# IF_GAIN.net
KiCad netlist of a schematic drawn in Altium Designer
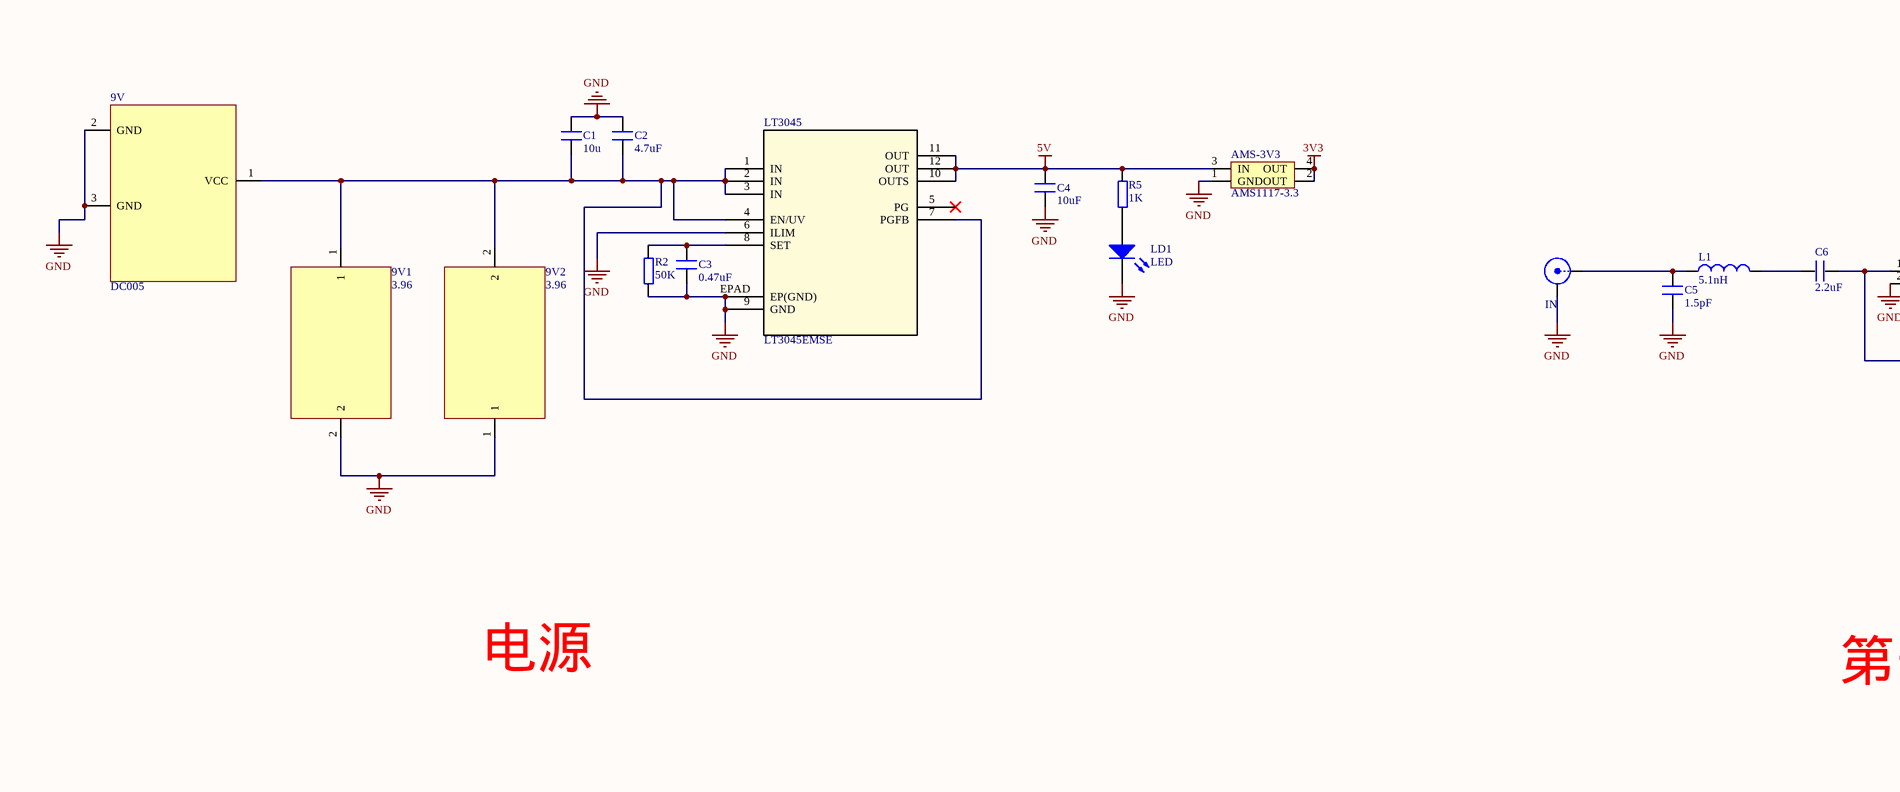
[diagram p0: IF GAIN].SchDoc, top left]
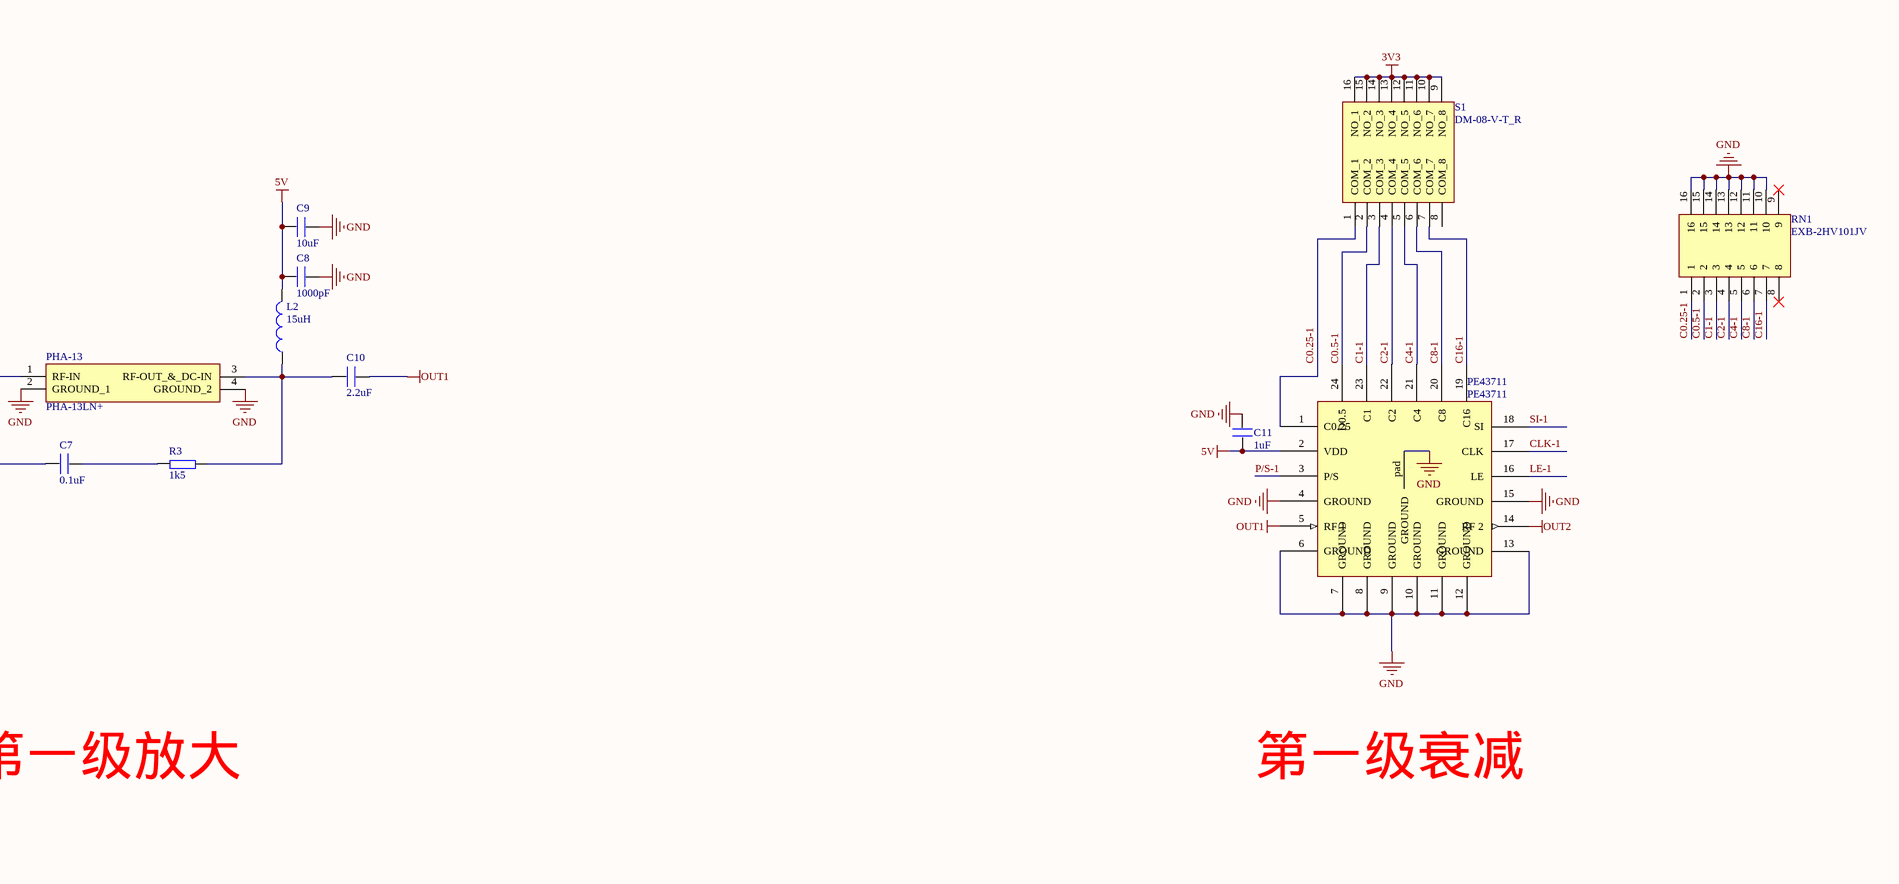
[diagram p1: IF GAIN].SchDoc, top right]
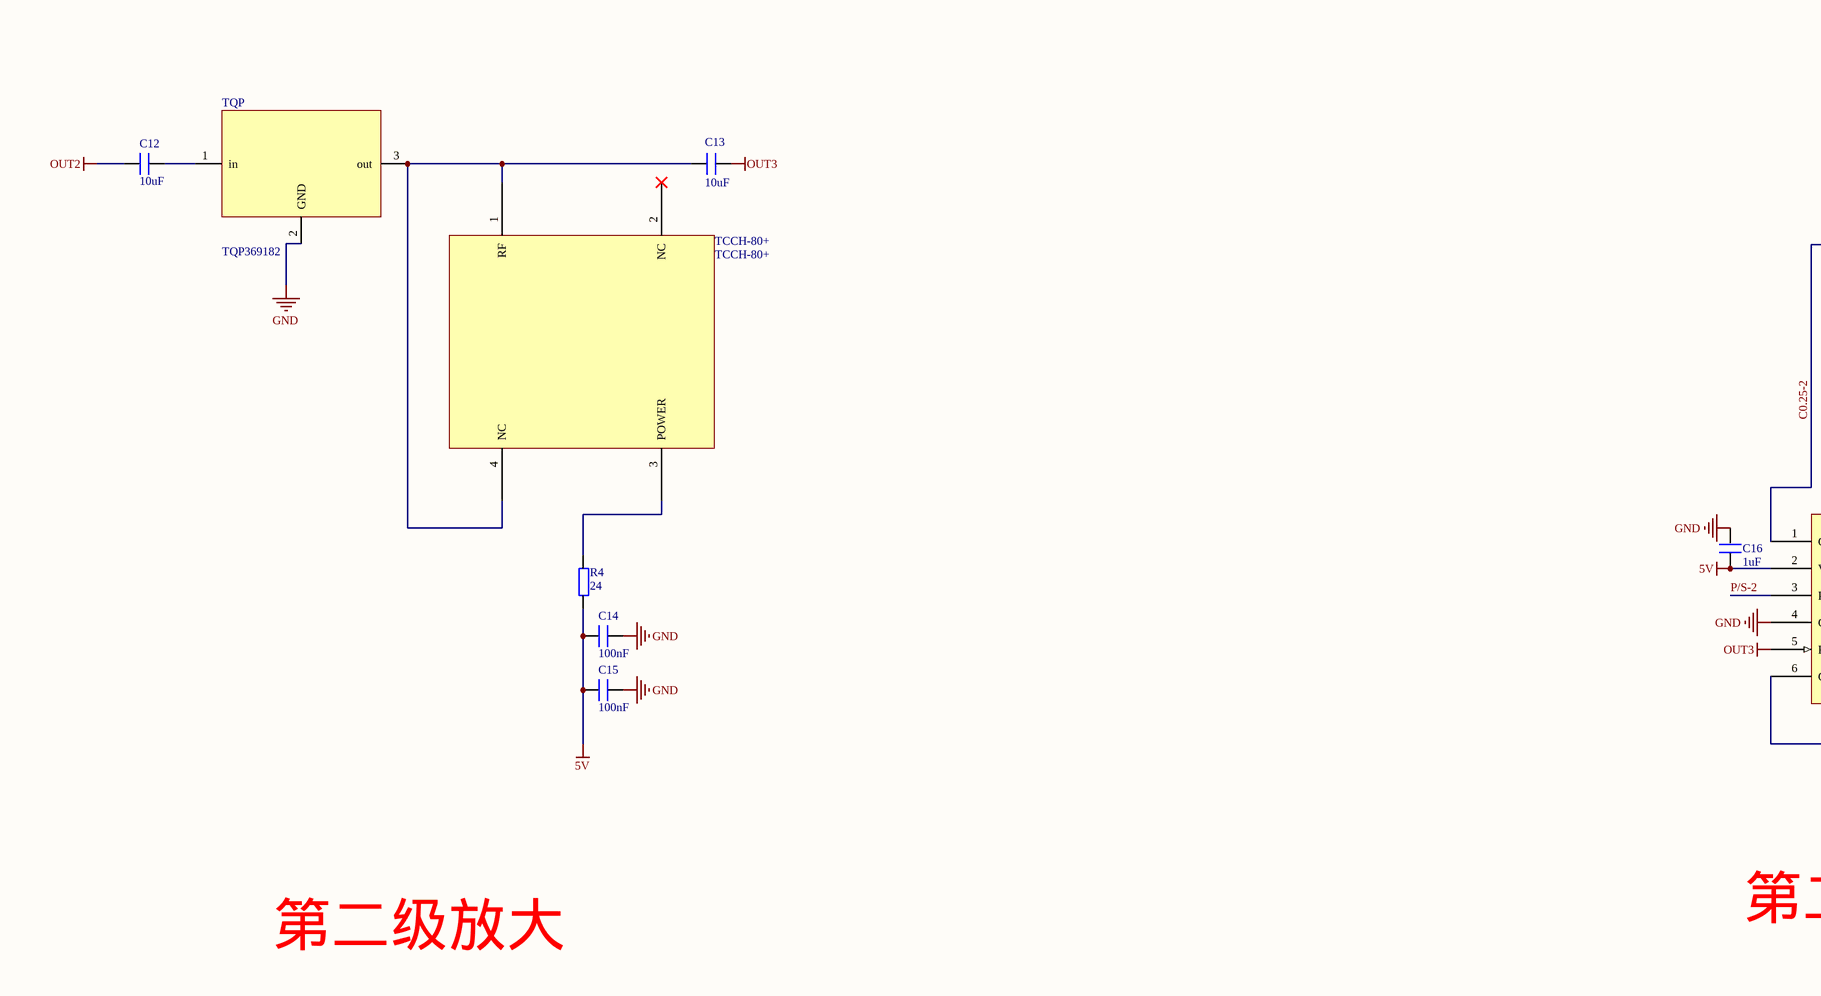
[diagram p2: IF GAIN].SchDoc, bottom left]
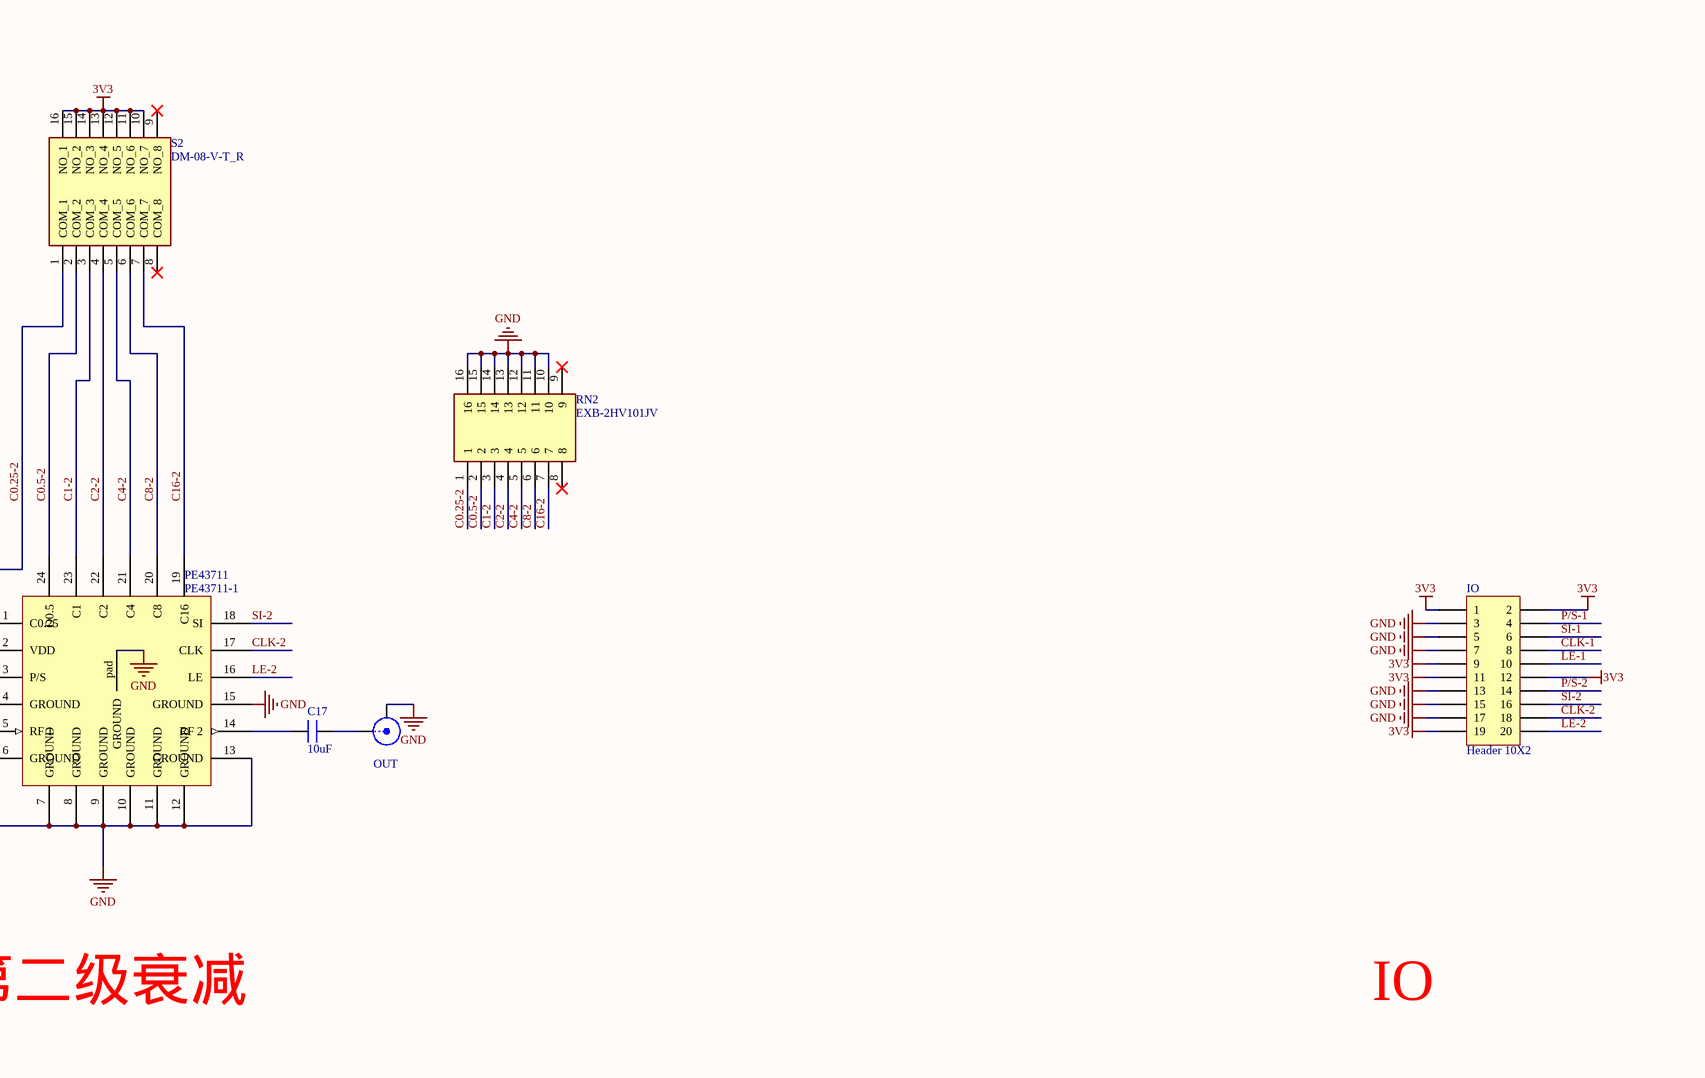
[diagram p3: IF GAIN].SchDoc, bottom right]

(export (version "E")
  (design (tool "Eeschema 10.0.6"))
  (components
    (comp (ref "9V") (value "DC005") (footprint "DC10B") (libsource (lib "MYLIB") (part "DC005")))
    (comp (ref "9V1") (value "3.96") (footprint "3.96") (libsource (lib "") (part "3.96_1")))
    (comp (ref "9V2") (value "3.96") (footprint "3.96") (libsource (lib "MYLIB") (part "3.96")))
    (comp (ref "AMS-3V3")
      (value "AMS1117-3.3")
      (footprint "AMS1117")
      (libsource (lib "MYLIB") (part "AMS1117"))
    )
    (comp (ref "C1")
      (value "10u")
      (footprint "0603C")
      (description "Capacitor")
      (libsource (lib "MYLIB") (part "C"))
    )
    (comp (ref "C2")
      (value "4.7uF")
      (footprint "0603C")
      (description "Capacitor")
      (libsource (lib "MYLIB") (part "C"))
    )
    (comp (ref "C3")
      (value "0.47uF")
      (footprint "0402")
      (description "Capacitor")
      (libsource (lib "MYLIB") (part "C"))
    )
    (comp (ref "C4")
      (value "10uF")
      (footprint "0402")
      (description "Capacitor")
      (libsource (lib "MYLIB") (part "C"))
    )
    (comp (ref "C5")
      (value "1.5pF")
      (footprint "0402")
      (description "Capacitor")
      (libsource (lib "MYLIB") (part "C"))
    )
    (comp (ref "C6")
      (value "2.2uF")
      (footprint "0402")
      (description "Capacitor")
      (libsource (lib "MYLIB") (part "C"))
    )
    (comp (ref "C7")
      (value "0.1uF")
      (footprint "0402")
      (description "Capacitor")
      (libsource (lib "MYLIB") (part "C"))
    )
    (comp (ref "C8")
      (value "1000pF")
      (footprint "0402")
      (description "Capacitor")
      (libsource (lib "MYLIB") (part "C"))
    )
    (comp (ref "C9")
      (value "10uF")
      (footprint "0603C")
      (description "Capacitor")
      (libsource (lib "MYLIB") (part "C"))
    )
    (comp (ref "C10")
      (value "2.2uF")
      (footprint "0402")
      (description "Capacitor")
      (libsource (lib "MYLIB") (part "C"))
    )
    (comp (ref "C11")
      (value "1uF")
      (footprint "0402")
      (description "Capacitor")
      (libsource (lib "MYLIB") (part "C"))
    )
    (comp (ref "C12")
      (value "10uF")
      (footprint "0402")
      (description "Capacitor")
      (libsource (lib "MYLIB") (part "C"))
    )
    (comp (ref "C13")
      (value "10uF")
      (footprint "0402")
      (description "Capacitor")
      (libsource (lib "MYLIB") (part "C"))
    )
    (comp (ref "C14")
      (value "100nF")
      (footprint "0603C")
      (description "Capacitor")
      (libsource (lib "MYLIB") (part "C"))
    )
    (comp (ref "C15")
      (value "100nF")
      (footprint "0603C")
      (description "Capacitor")
      (libsource (lib "MYLIB") (part "C"))
    )
    (comp (ref "C16")
      (value "1uF")
      (footprint "0402")
      (description "Capacitor")
      (libsource (lib "MYLIB") (part "C"))
    )
    (comp (ref "C17")
      (value "10uF")
      (footprint "0402")
      (description "Capacitor")
      (libsource (lib "MYLIB") (part "C"))
    )
    (comp (ref "IN")
      (value "SMA")
      (footprint "SMA")
      (description "SMA Connector")
      (libsource (lib "MYLIB") (part "SMA"))
    )
    (comp (ref "IO")
      (value "Header 10X2")
      (footprint "HDR2X10")
      (description "Header, 10-Pin, Dual row")
      (fields (field (name "PUBLISHER") "Altium Limited"))
      (libsource (lib "Miscellaneous Connectors") (part "Header 10X2"))
    )
    (comp (ref "L1")
      (value "5.1nH")
      (footprint "0402")
      (description "Inductor")
      (fields (field (name "PUBLISHER") "Altium Limited"))
      (libsource (lib "MYLIB") (part "Inductor"))
    )
    (comp (ref "L2")
      (value "15uH")
      (footprint "1206C")
      (description "Inductor")
      (fields (field (name "PUBLISHER") "Altium Limited"))
      (libsource (lib "MYLIB") (part "Inductor"))
    )
    (comp (ref "LD1")
      (value "LED")
      (footprint "SMDLED")
      (description "Typical RED, GREEN, YELLOW, AMBER GaAs LED")
      (fields (field (name "PUBLISHER") "Altium Limited"))
      (libsource (lib "MYLIB") (part "LED"))
    )
    (comp (ref "LT3045")
      (value "LT3045EMSE")
      (footprint "MSOP12-MSE-RevG_ADI")
      (description "No Description Available")
      (fields (field (name "COPYRIGHT") "Copyright (C) 2018 Accelerated Designs. All rights reserved"))
      (libsource (lib "MYLIB") (part "LT3045EMSE"))
    )
    (comp (ref "OUT")
      (value "SMA")
      (footprint "SMA")
      (description "SMA Connector")
      (libsource (lib "MYLIB") (part "SMA"))
    )
    (comp (ref "PE43711") (value "PE43711") (footprint "PE43711") (libsource (lib "MYLIB") (part "PE43711")))
    (comp (ref "PE43711-1")
      (value "PE43711")
      (footprint "PE43711")
      (libsource (lib "MYLIB") (part "PE43711"))
    )
    (comp (ref "PHA-13")
      (value "PHA-13LN+")
      (footprint "MYLIB:PHA13LN")
      (description "Integrated Circuit")
      (fields (field (name "MOUSER PART NUMBER") "139-PHA-13LN"))
      (libsource (lib "*") (part "PHA-13LN+"))
    )
    (comp (ref "R2")
      (value "50K")
      (footprint "0402")
      (description "Resistor")
      (libsource (lib "MYLIB") (part "Resistor"))
    )
    (comp (ref "R3")
      (value "1k5")
      (footprint "0402")
      (description "Resistor")
      (libsource (lib "MYLIB") (part "Resistor"))
    )
    (comp (ref "R4")
      (value "24")
      (footprint "1206")
      (description "Resistor")
      (libsource (lib "MYLIB") (part "Resistor"))
    )
    (comp (ref "R5")
      (value "1K")
      (footprint "0603R")
      (description "Resistor")
      (libsource (lib "MYLIB") (part "Resistor"))
    )
    (comp (ref "RN1")
      (value "EXB-2HV101JV")
      (footprint "MYLIB:EXB2HV101JV")
      (description "Resistor Network")
      (fields (field (name "MOUSER PART NUMBER") "667-EXB-2HV101JV"))
      (libsource (lib "MYLIB") (part "EXB-2HV101JV"))
    )
    (comp (ref "RN2")
      (value "EXB-2HV101JV")
      (footprint "MYLIB:EXB2HV101JV")
      (description "Resistor Network")
      (fields (field (name "MOUSER PART NUMBER") "667-EXB-2HV101JV"))
      (libsource (lib "MYLIB") (part "EXB-2HV101JV"))
    )
    (comp (ref "S1")
      (value "DM-08-V-T_R")
      (footprint "MYLIB:DM08VTR")
      (description "Switch")
      (fields (field (name "MANUFACTURER_PART_NUMBER") "DM-08-V-T/R"))
      (libsource (lib "*") (part "DM-08-V-T_R"))
    )
    (comp (ref "S2")
      (value "DM-08-V-T_R")
      (footprint "MYLIB:DM08VTR")
      (description "Switch")
      (fields (field (name "MANUFACTURER_PART_NUMBER") "DM-08-V-T/R"))
      (libsource (lib "MYLIB") (part "DM-08-V-T_R"))
    )
    (comp (ref "TCCH-80+")
      (value "TCCH-80+")
      (footprint "GU1604")
      (libsource (lib "MYLIB") (part "TCCH-80+"))
    )
    (comp (ref "TQP") (value "TQP369182") (footprint "SOT89_M") (libsource (lib "MYLIB") (part "TQP369182")))
  )
  (nets
    (net (code "1") (name "/C0.5-1") (class "Default")
      (node (ref "PE43711") (pin "24") (pinfunction "D0.5_24") (pintype "passive"))
      (node (ref "RN1") (pin "2") (pinfunction "2_2") (pintype "passive"))
      (node (ref "S1") (pin "2") (pinfunction "COM_2_2") (pintype "passive"))
    )
    (net (code "2") (name "/C0.5-2") (class "Default")
      (node (ref "PE43711-1") (pin "24") (pinfunction "D0.5_24") (pintype "passive"))
      (node (ref "RN2") (pin "2") (pinfunction "2_2") (pintype "passive"))
      (node (ref "S2") (pin "2") (pinfunction "COM_2_2") (pintype "passive"))
    )
    (net (code "3") (name "/C0.25-1") (class "Default")
      (node (ref "PE43711") (pin "1") (pinfunction "C0.25_1") (pintype "open_collector"))
      (node (ref "RN1") (pin "1") (pinfunction "1_1") (pintype "passive"))
      (node (ref "S1") (pin "1") (pinfunction "COM_1_1") (pintype "passive"))
    )
    (net (code "4") (name "/C0.25-2") (class "Default")
      (node (ref "PE43711-1") (pin "1") (pinfunction "C0.25_1") (pintype "open_collector"))
      (node (ref "RN2") (pin "1") (pinfunction "1_1") (pintype "passive"))
      (node (ref "S2") (pin "1") (pinfunction "COM_1_1") (pintype "passive"))
    )
    (net (code "5") (name "/C1-1") (class "Default")
      (node (ref "PE43711") (pin "23") (pinfunction "C1_23") (pintype "passive"))
      (node (ref "RN1") (pin "3") (pinfunction "3_3") (pintype "passive"))
      (node (ref "S1") (pin "3") (pinfunction "COM_3_3") (pintype "passive"))
    )
    (net (code "6") (name "/C1-2") (class "Default")
      (node (ref "PE43711-1") (pin "23") (pinfunction "C1_23") (pintype "passive"))
      (node (ref "RN2") (pin "3") (pinfunction "3_3") (pintype "passive"))
      (node (ref "S2") (pin "3") (pinfunction "COM_3_3") (pintype "passive"))
    )
    (net (code "7") (name "/C2-1") (class "Default")
      (node (ref "PE43711") (pin "22") (pinfunction "C2_22") (pintype "passive"))
      (node (ref "RN1") (pin "4") (pinfunction "4_4") (pintype "passive"))
      (node (ref "S1") (pin "4") (pinfunction "COM_4_4") (pintype "passive"))
    )
    (net (code "8") (name "/C2-2") (class "Default")
      (node (ref "PE43711-1") (pin "22") (pinfunction "C2_22") (pintype "passive"))
      (node (ref "RN2") (pin "4") (pinfunction "4_4") (pintype "passive"))
      (node (ref "S2") (pin "4") (pinfunction "COM_4_4") (pintype "passive"))
    )
    (net (code "9") (name "/C4-1") (class "Default")
      (node (ref "PE43711") (pin "21") (pinfunction "C4_21") (pintype "passive"))
      (node (ref "RN1") (pin "5") (pinfunction "5_5") (pintype "passive"))
      (node (ref "S1") (pin "5") (pinfunction "COM_5_5") (pintype "passive"))
    )
    (net (code "10") (name "/C4-2") (class "Default")
      (node (ref "PE43711-1") (pin "21") (pinfunction "C4_21") (pintype "passive"))
      (node (ref "RN2") (pin "5") (pinfunction "5_5") (pintype "passive"))
      (node (ref "S2") (pin "5") (pinfunction "COM_5_5") (pintype "passive"))
    )
    (net (code "11") (name "/C8-1") (class "Default")
      (node (ref "PE43711") (pin "20") (pinfunction "C8_20") (pintype "passive"))
      (node (ref "RN1") (pin "6") (pinfunction "6_6") (pintype "passive"))
      (node (ref "S1") (pin "6") (pinfunction "COM_6_6") (pintype "passive"))
    )
    (net (code "12") (name "/C8-2") (class "Default")
      (node (ref "PE43711-1") (pin "20") (pinfunction "C8_20") (pintype "passive"))
      (node (ref "RN2") (pin "6") (pinfunction "6_6") (pintype "passive"))
      (node (ref "S2") (pin "6") (pinfunction "COM_6_6") (pintype "passive"))
    )
    (net (code "13") (name "/C16-1") (class "Default")
      (node (ref "PE43711") (pin "19") (pinfunction "C16_19") (pintype "open_collector"))
      (node (ref "RN1") (pin "7") (pinfunction "7_7") (pintype "passive"))
      (node (ref "S1") (pin "7") (pinfunction "COM_7_7") (pintype "passive"))
    )
    (net (code "14") (name "/C16-2") (class "Default")
      (node (ref "PE43711-1") (pin "19") (pinfunction "C16_19") (pintype "open_collector"))
      (node (ref "RN2") (pin "7") (pinfunction "7_7") (pintype "passive"))
      (node (ref "S2") (pin "7") (pinfunction "COM_7_7") (pintype "passive"))
    )
    (net (code "15") (name "/CLK-1") (class "Default")
      (node (ref "IO") (pin "8") (pinfunction "8_8") (pintype "passive"))
      (node (ref "PE43711") (pin "17") (pinfunction "CLK_17") (pintype "passive"))
    )
    (net (code "16") (name "/CLK-2") (class "Default")
      (node (ref "IO") (pin "18") (pinfunction "18_18") (pintype "passive"))
      (node (ref "PE43711-1") (pin "17") (pinfunction "CLK_17") (pintype "passive"))
    )
    (net (code "17") (name "/LE-1") (class "Default")
      (node (ref "IO") (pin "10") (pinfunction "10_10") (pintype "passive"))
      (node (ref "PE43711") (pin "16") (pinfunction "LE_16") (pintype "passive"))
    )
    (net (code "18") (name "/LE-2") (class "Default")
      (node (ref "IO") (pin "20") (pinfunction "20_20") (pintype "passive"))
      (node (ref "PE43711-1") (pin "16") (pinfunction "LE_16") (pintype "passive"))
    )
    (net (code "19") (name "/P{slash}S-1") (class "Default")
      (node (ref "IO") (pin "4") (pinfunction "4_4") (pintype "passive"))
      (node (ref "PE43711") (pin "3") (pinfunction "P/S_3") (pintype "passive"))
    )
    (net (code "20") (name "/P{slash}S-2") (class "Default")
      (node (ref "IO") (pin "14") (pinfunction "14_14") (pintype "passive"))
      (node (ref "PE43711-1") (pin "3") (pinfunction "P/S_3") (pintype "passive"))
    )
    (net (code "21") (name "/SI-1") (class "Default")
      (node (ref "IO") (pin "6") (pinfunction "6_6") (pintype "passive"))
      (node (ref "PE43711") (pin "18") (pinfunction "SI_18") (pintype "passive"))
    )
    (net (code "22") (name "/SI-2") (class "Default")
      (node (ref "IO") (pin "16") (pinfunction "16_16") (pintype "passive"))
      (node (ref "PE43711-1") (pin "18") (pinfunction "SI_18") (pintype "passive"))
    )
    (net (code "23") (name "3V3") (class "Default")
      (node (ref "AMS-3V3") (pin "2") (pinfunction "OUT_2") (pintype "passive"))
      (node (ref "AMS-3V3") (pin "4") (pinfunction "OUT_4") (pintype "passive"))
      (node (ref "IO") (pin "1") (pinfunction "1_1") (pintype "passive"))
      (node (ref "IO") (pin "11") (pinfunction "11_11") (pintype "passive"))
      (node (ref "IO") (pin "12") (pinfunction "12_12") (pintype "passive"))
      (node (ref "IO") (pin "19") (pinfunction "19_19") (pintype "passive"))
      (node (ref "IO") (pin "2") (pinfunction "2_2") (pintype "passive"))
      (node (ref "IO") (pin "9") (pinfunction "9_9") (pintype "passive"))
      (node (ref "S1") (pin "10") (pinfunction "NO_7_10") (pintype "passive"))
      (node (ref "S1") (pin "11") (pinfunction "NO_6_11") (pintype "passive"))
      (node (ref "S1") (pin "12") (pinfunction "NO_5_12") (pintype "passive"))
      (node (ref "S1") (pin "13") (pinfunction "NO_4_13") (pintype "passive"))
      (node (ref "S1") (pin "14") (pinfunction "NO_3_14") (pintype "passive"))
      (node (ref "S1") (pin "15") (pinfunction "NO_2_15") (pintype "passive"))
      (node (ref "S1") (pin "16") (pinfunction "NO_1_16") (pintype "passive"))
      (node (ref "S1") (pin "9") (pinfunction "NO_8_9") (pintype "passive"))
      (node (ref "S2") (pin "10") (pinfunction "NO_7_10") (pintype "passive"))
      (node (ref "S2") (pin "11") (pinfunction "NO_6_11") (pintype "passive"))
      (node (ref "S2") (pin "12") (pinfunction "NO_5_12") (pintype "passive"))
      (node (ref "S2") (pin "13") (pinfunction "NO_4_13") (pintype "passive"))
      (node (ref "S2") (pin "14") (pinfunction "NO_3_14") (pintype "passive"))
      (node (ref "S2") (pin "15") (pinfunction "NO_2_15") (pintype "passive"))
      (node (ref "S2") (pin "16") (pinfunction "NO_1_16") (pintype "passive"))
    )
    (net (code "24") (name "5V") (class "Default")
      (node (ref "AMS-3V3") (pin "3") (pinfunction "IN_3") (pintype "passive"))
      (node (ref "C11") (pin "1") (pintype "passive"))
      (node (ref "C14") (pin "1") (pintype "passive"))
      (node (ref "C15") (pin "1") (pintype "passive"))
      (node (ref "C16") (pin "1") (pintype "passive"))
      (node (ref "C4") (pin "2") (pintype "passive"))
      (node (ref "C8") (pin "2") (pintype "passive"))
      (node (ref "C9") (pin "2") (pintype "passive"))
      (node (ref "L2") (pin "2") (pinfunction "2_2") (pintype "passive"))
      (node (ref "LT3045") (pin "10") (pinfunction "OUTS_10") (pintype "passive"))
      (node (ref "LT3045") (pin "11") (pinfunction "OUT_11") (pintype "passive"))
      (node (ref "LT3045") (pin "12") (pinfunction "OUT_12") (pintype "passive"))
      (node (ref "PE43711") (pin "2") (pinfunction "VDD_2") (pintype "power_in"))
      (node (ref "PE43711-1") (pin "2") (pinfunction "VDD_2") (pintype "power_in"))
      (node (ref "R4") (pin "1") (pintype "passive"))
      (node (ref "R5") (pin "2") (pintype "passive"))
    )
    (net (code "25") (name "GND") (class "Default")
      (node (ref "9V") (pin "2") (pinfunction "GND_2") (pintype "passive"))
      (node (ref "9V") (pin "3") (pinfunction "GND_3") (pintype "passive"))
      (node (ref "9V1") (pin "2") (pinfunction "2_2") (pintype "passive"))
      (node (ref "9V2") (pin "1") (pinfunction "1_1") (pintype "passive"))
      (node (ref "AMS-3V3") (pin "1") (pinfunction "GND_1") (pintype "passive"))
      (node (ref "C1") (pin "2") (pintype "passive"))
      (node (ref "C11") (pin "2") (pintype "passive"))
      (node (ref "C14") (pin "2") (pintype "passive"))
      (node (ref "C15") (pin "2") (pintype "passive"))
      (node (ref "C16") (pin "2") (pintype "passive"))
      (node (ref "C2") (pin "2") (pintype "passive"))
      (node (ref "C3") (pin "1") (pintype "passive"))
      (node (ref "C4") (pin "1") (pintype "passive"))
      (node (ref "C5") (pin "1") (pintype "passive"))
      (node (ref "C8") (pin "1") (pintype "passive"))
      (node (ref "C9") (pin "1") (pintype "passive"))
      (node (ref "IN") (pin "2") (pinfunction "Y_2") (pintype "passive"))
      (node (ref "IO") (pin "13") (pinfunction "13_13") (pintype "passive"))
      (node (ref "IO") (pin "15") (pinfunction "15_15") (pintype "passive"))
      (node (ref "IO") (pin "17") (pinfunction "17_17") (pintype "passive"))
      (node (ref "IO") (pin "3") (pinfunction "3_3") (pintype "passive"))
      (node (ref "IO") (pin "5") (pinfunction "5_5") (pintype "passive"))
      (node (ref "IO") (pin "7") (pinfunction "7_7") (pintype "passive"))
      (node (ref "LD1") (pin "2") (pinfunction "K_2") (pintype "passive"))
      (node (ref "LT3045") (pin "6") (pinfunction "ILIM_6") (pintype "passive"))
      (node (ref "LT3045") (pin "9") (pinfunction "GND_9") (pintype "passive"))
      (node (ref "LT3045") (pin "EPAD") (pinfunction "EP(GND)_EPAD") (pintype "passive"))
      (node (ref "OUT") (pin "2") (pinfunction "Y_2") (pintype "passive"))
      (node (ref "PE43711") (pin "10") (pinfunction "GROUND_10") (pintype "passive"))
      (node (ref "PE43711") (pin "11") (pinfunction "GROUND_11") (pintype "passive"))
      (node (ref "PE43711") (pin "12") (pinfunction "GROUND_12") (pintype "passive"))
      (node (ref "PE43711") (pin "13") (pinfunction "GROUND_13") (pintype "passive"))
      (node (ref "PE43711") (pin "15") (pinfunction "GROUND_15") (pintype "passive"))
      (node (ref "PE43711") (pin "4") (pinfunction "GROUND_4") (pintype "passive"))
      (node (ref "PE43711") (pin "6") (pinfunction "GROUND_6") (pintype "passive"))
      (node (ref "PE43711") (pin "7") (pinfunction "GROUND_7") (pintype "passive"))
      (node (ref "PE43711") (pin "8") (pinfunction "GROUND_8") (pintype "passive"))
      (node (ref "PE43711") (pin "9") (pinfunction "GROUND_9") (pintype "passive"))
      (node (ref "PE43711") (pin "pad") (pinfunction "GROUND_pad") (pintype "passive"))
      (node (ref "PE43711-1") (pin "10") (pinfunction "GROUND_10") (pintype "passive"))
      (node (ref "PE43711-1") (pin "11") (pinfunction "GROUND_11") (pintype "passive"))
      (node (ref "PE43711-1") (pin "12") (pinfunction "GROUND_12") (pintype "passive"))
      (node (ref "PE43711-1") (pin "13") (pinfunction "GROUND_13") (pintype "passive"))
      (node (ref "PE43711-1") (pin "15") (pinfunction "GROUND_15") (pintype "passive"))
      (node (ref "PE43711-1") (pin "4") (pinfunction "GROUND_4") (pintype "passive"))
      (node (ref "PE43711-1") (pin "6") (pinfunction "GROUND_6") (pintype "passive"))
      (node (ref "PE43711-1") (pin "7") (pinfunction "GROUND_7") (pintype "passive"))
      (node (ref "PE43711-1") (pin "8") (pinfunction "GROUND_8") (pintype "passive"))
      (node (ref "PE43711-1") (pin "9") (pinfunction "GROUND_9") (pintype "passive"))
      (node (ref "PE43711-1") (pin "pad") (pinfunction "GROUND_pad") (pintype "passive"))
      (node (ref "PHA-13") (pin "2") (pinfunction "GROUND_1_2") (pintype "passive"))
      (node (ref "PHA-13") (pin "4") (pinfunction "GROUND_2_4") (pintype "passive"))
      (node (ref "R2") (pin "1") (pintype "passive"))
      (node (ref "RN1") (pin "10") (pinfunction "10_10") (pintype "passive"))
      (node (ref "RN1") (pin "11") (pinfunction "11_11") (pintype "passive"))
      (node (ref "RN1") (pin "12") (pinfunction "12_12") (pintype "passive"))
      (node (ref "RN1") (pin "13") (pinfunction "13_13") (pintype "passive"))
      (node (ref "RN1") (pin "14") (pinfunction "14_14") (pintype "passive"))
      (node (ref "RN1") (pin "15") (pinfunction "15_15") (pintype "passive"))
      (node (ref "RN1") (pin "16") (pinfunction "16_16") (pintype "passive"))
      (node (ref "RN2") (pin "10") (pinfunction "10_10") (pintype "passive"))
      (node (ref "RN2") (pin "11") (pinfunction "11_11") (pintype "passive"))
      (node (ref "RN2") (pin "12") (pinfunction "12_12") (pintype "passive"))
      (node (ref "RN2") (pin "13") (pinfunction "13_13") (pintype "passive"))
      (node (ref "RN2") (pin "14") (pinfunction "14_14") (pintype "passive"))
      (node (ref "RN2") (pin "15") (pinfunction "15_15") (pintype "passive"))
      (node (ref "RN2") (pin "16") (pinfunction "16_16") (pintype "passive"))
      (node (ref "TQP") (pin "2") (pinfunction "GND_2") (pintype "passive"))
    )
    (net (code "26") (name "Net-(9V-VCC)") (class "Default")
      (node (ref "9V") (pin "1") (pinfunction "VCC_1") (pintype "passive"))
      (node (ref "9V1") (pin "1") (pinfunction "1_1") (pintype "passive"))
      (node (ref "9V2") (pin "2") (pinfunction "2_2") (pintype "passive"))
      (node (ref "C1") (pin "1") (pintype "passive"))
      (node (ref "C2") (pin "1") (pintype "passive"))
      (node (ref "LT3045") (pin "1") (pinfunction "IN_1") (pintype "passive"))
      (node (ref "LT3045") (pin "2") (pinfunction "IN_2") (pintype "passive"))
      (node (ref "LT3045") (pin "3") (pinfunction "IN_3") (pintype "passive"))
      (node (ref "LT3045") (pin "4") (pinfunction "EN/UV_4") (pintype "passive"))
      (node (ref "LT3045") (pin "7") (pinfunction "PGFB_7") (pintype "passive"))
    )
    (net (code "27") (name "Net-(C6-Pad2)") (class "Default")
      (node (ref "C6") (pin "2") (pintype "passive"))
      (node (ref "L1") (pin "2") (pinfunction "2_2") (pintype "passive"))
    )
    (net (code "28") (name "Net-(C7-Pad1)") (class "Default")
      (node (ref "C7") (pin "1") (pintype "passive"))
      (node (ref "R3") (pin "1") (pintype "passive"))
    )
    (net (code "29") (name "Net-(IN-X)") (class "Default")
      (node (ref "C5") (pin "2") (pintype "passive"))
      (node (ref "IN") (pin "1") (pinfunction "X_1") (pintype "passive"))
      (node (ref "L1") (pin "1") (pinfunction "1_1") (pintype "passive"))
    )
    (net (code "30") (name "Net-(LD1-A)") (class "Default")
      (node (ref "LD1") (pin "1") (pinfunction "A_1") (pintype "passive"))
      (node (ref "R5") (pin "1") (pintype "passive"))
    )
    (net (code "31") (name "Net-(LT3045-SET)") (class "Default")
      (node (ref "C3") (pin "2") (pintype "passive"))
      (node (ref "LT3045") (pin "8") (pinfunction "SET_8") (pintype "passive"))
      (node (ref "R2") (pin "2") (pintype "passive"))
    )
    (net (code "32") (name "Net-(OUT-X)") (class "Default")
      (node (ref "C17") (pin "2") (pintype "passive"))
      (node (ref "OUT") (pin "1") (pinfunction "X_1") (pintype "passive"))
    )
    (net (code "33") (name "Net-(PE43711-1-RF_2)") (class "Default")
      (node (ref "C17") (pin "1") (pintype "passive"))
      (node (ref "PE43711-1") (pin "14") (pinfunction "RF_2_14") (pintype "output"))
    )
    (net (code "34") (name "Net-(PHA-13-RF-IN)") (class "Default")
      (node (ref "C6") (pin "1") (pintype "passive"))
      (node (ref "C7") (pin "2") (pintype "passive"))
      (node (ref "PHA-13") (pin "1") (pinfunction "RF-IN_1") (pintype "passive"))
    )
    (net (code "35") (name "Net-(PHA-13-RF-OUT_&_DC-IN)") (class "Default")
      (node (ref "C10") (pin "2") (pintype "passive"))
      (node (ref "L2") (pin "1") (pinfunction "1_1") (pintype "passive"))
      (node (ref "PHA-13") (pin "3") (pinfunction "RF-OUT_&_DC-IN_3") (pintype "passive"))
      (node (ref "R3") (pin "2") (pintype "passive"))
    )
    (net (code "36") (name "Net-(TCCH-80+-POWER)") (class "Default")
      (node (ref "R4") (pin "2") (pintype "passive"))
      (node (ref "TCCH-80+") (pin "3") (pinfunction "POWER_3") (pintype "passive"))
    )
    (net (code "37") (name "Net-(TCCH-80+-RF)") (class "Default")
      (node (ref "C13") (pin "1") (pintype "passive"))
      (node (ref "TCCH-80+") (pin "1") (pinfunction "RF_1") (pintype "passive"))
      (node (ref "TCCH-80+") (pin "4") (pinfunction "NC_4") (pintype "passive"))
      (node (ref "TQP") (pin "3") (pinfunction "out_3") (pintype "passive"))
    )
    (net (code "38") (name "Net-(TQP-in)") (class "Default")
      (node (ref "C12") (pin "2") (pintype "passive"))
      (node (ref "TQP") (pin "1") (pinfunction "in_1") (pintype "passive"))
    )
    (net (code "39") (name "OUT1") (class "Default")
      (node (ref "C10") (pin "1") (pintype "passive"))
      (node (ref "PE43711") (pin "5") (pinfunction "RF_1_5") (pintype "input"))
    )
    (net (code "40") (name "OUT2") (class "Default")
      (node (ref "C12") (pin "1") (pintype "passive"))
      (node (ref "PE43711") (pin "14") (pinfunction "RF_2_14") (pintype "output"))
    )
    (net (code "41") (name "OUT3") (class "Default")
      (node (ref "C13") (pin "2") (pintype "passive"))
      (node (ref "PE43711-1") (pin "5") (pinfunction "RF_1_5") (pintype "input"))
    )
    (net (code "42") (name "unconnected-(LT3045-PG-Pad5)") (class "Default")
      (node (ref "LT3045") (pin "5") (pinfunction "PG_5") (pintype "passive+no_connect"))
    )
    (net (code "43") (name "unconnected-(RN1-Pad8)") (class "Default")
      (node (ref "RN1") (pin "8") (pinfunction "8_8") (pintype "passive+no_connect"))
    )
    (net (code "44") (name "unconnected-(RN1-Pad9)") (class "Default")
      (node (ref "RN1") (pin "9") (pinfunction "9_9") (pintype "passive+no_connect"))
    )
    (net (code "45") (name "unconnected-(RN2-Pad8)") (class "Default")
      (node (ref "RN2") (pin "8") (pinfunction "8_8") (pintype "passive+no_connect"))
    )
    (net (code "46") (name "unconnected-(RN2-Pad9)") (class "Default")
      (node (ref "RN2") (pin "9") (pinfunction "9_9") (pintype "passive+no_connect"))
    )
    (net (code "47") (name "unconnected-(S1-COM_8-Pad8)") (class "Default")
      (node (ref "S1") (pin "8") (pinfunction "COM_8_8") (pintype "passive"))
    )
    (net (code "48") (name "unconnected-(S2-COM_8-Pad8)") (class "Default")
      (node (ref "S2") (pin "8") (pinfunction "COM_8_8") (pintype "passive+no_connect"))
    )
    (net (code "49") (name "unconnected-(S2-NO_8-Pad9)") (class "Default")
      (node (ref "S2") (pin "9") (pinfunction "NO_8_9") (pintype "passive+no_connect"))
    )
    (net (code "50") (name "unconnected-(TCCH-80+-NC-Pad2)") (class "Default")
      (node (ref "TCCH-80+") (pin "2") (pinfunction "NC_2") (pintype "passive+no_connect"))
    )
  )
)
